# power_supply.net
KiCad netlist of a schematic drawn in Altium Designer
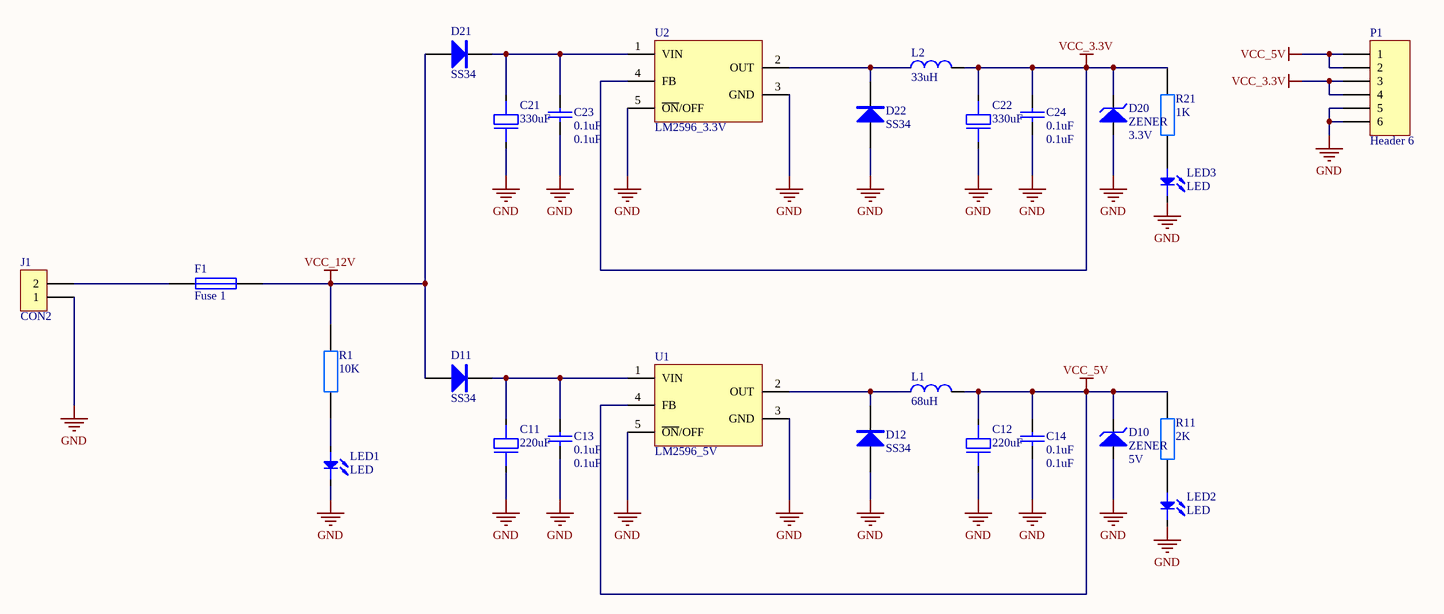
[diagram p0: power supply.SchDoc]

(export (version "E")
  (design (tool "Eeschema 10.0.6"))
  (components
    (comp (ref "C11")
      (value "220uF")
      (footprint "SMD-EC-F10")
      (libsource (lib "common") (part "Electrolytic CAP"))
    )
    (comp (ref "C12")
      (value "220uF")
      (footprint "SMD-EC-F10")
      (libsource (lib "common") (part "Electrolytic CAP"))
    )
    (comp (ref "C13")
      (value "0.1uF")
      (footprint "0805C")
      (fields (field (name "ALTIUM_VALUE") "0.1uF"))
      (libsource (lib "common") (part "CAP"))
    )
    (comp (ref "C14")
      (value "0.1uF")
      (footprint "0805C")
      (fields (field (name "ALTIUM_VALUE") "0.1uF"))
      (libsource (lib "common") (part "CAP"))
    )
    (comp (ref "C21")
      (value "330uF")
      (footprint "SMD-EC-F10")
      (libsource (lib "common") (part "Electrolytic CAP"))
    )
    (comp (ref "C22")
      (value "330uF")
      (footprint "SMD-EC-F10")
      (libsource (lib "common") (part "Electrolytic CAP"))
    )
    (comp (ref "C23")
      (value "0.1uF")
      (footprint "0805C")
      (fields (field (name "ALTIUM_VALUE") "0.1uF"))
      (libsource (lib "common") (part "CAP"))
    )
    (comp (ref "C24")
      (value "0.1uF")
      (footprint "0805C")
      (fields (field (name "ALTIUM_VALUE") "0.1uF"))
      (libsource (lib "common") (part "CAP"))
    )
    (comp (ref "D10")
      (value "ZENER")
      (footprint "1206D")
      (fields (field (name "ALTIUM_VALUE") "5V"))
      (libsource (lib "common") (part "ZENER"))
    )
    (comp (ref "D11")
      (value "SS34")
      (footprint "SMA")
      (description "Diode")
      (libsource (lib "common") (part "SS14"))
    )
    (comp (ref "D12")
      (value "SS34")
      (footprint "SMA")
      (description "Diode")
      (libsource (lib "common") (part "SS14"))
    )
    (comp (ref "D20")
      (value "ZENER")
      (footprint "1206D")
      (fields (field (name "ALTIUM_VALUE") "3.3V"))
      (libsource (lib "common") (part "ZENER"))
    )
    (comp (ref "D21")
      (value "SS34")
      (footprint "SMA")
      (description "Diode")
      (libsource (lib "common") (part "SS14"))
    )
    (comp (ref "D22")
      (value "SS34")
      (footprint "SMA")
      (description "Diode")
      (libsource (lib "common") (part "SS14"))
    )
    (comp (ref "F1")
      (value "Fuse 1")
      (footprint "FUSE1")
      (description "Fuse")
      (fields (field (name "PUBLISHER") "Altium Limited"))
      (libsource (lib "common") (part "Fuse 1"))
    )
    (comp (ref "J1") (value "CON2") (footprint "con2") (libsource (lib "common") (part "CON2")))
    (comp (ref "L1") (value "68uH") (footprint "12x12") (libsource (lib "common") (part "Inductance")))
    (comp (ref "L2") (value "33uH") (footprint "12x12") (libsource (lib "common") (part "Inductance")))
    (comp (ref "LED1") (value "LED") (footprint "3528 led") (libsource (lib "common") (part "LED")))
    (comp (ref "LED2") (value "LED") (footprint "3528 led") (libsource (lib "common") (part "LED")))
    (comp (ref "LED3") (value "LED") (footprint "3528 led") (libsource (lib "common") (part "LED")))
    (comp (ref "P1")
      (value "Header 6")
      (footprint "HDR1X6")
      (description "Header, 6-Pin")
      (fields (field (name "PUBLISHER") "Altium Limited"))
      (libsource (lib "Miscellaneous Connectors") (part "Header 6"))
    )
    (comp (ref "R1")
      (value "10K")
      (footprint "0805")
      (description "RES")
      (libsource (lib "common") (part "RES"))
    )
    (comp (ref "R11")
      (value "2K")
      (footprint "0805")
      (description "RES")
      (libsource (lib "common") (part "RES"))
    )
    (comp (ref "R21")
      (value "1K")
      (footprint "0805")
      (description "RES")
      (libsource (lib "common") (part "RES"))
    )
    (comp (ref "U1")
      (value "LM2596_5V")
      (footprint "平面IC:TO-263")
      (description "IC-power")
      (libsource (lib "common") (part "LM2596"))
    )
    (comp (ref "U2")
      (value "LM2596_3.3V")
      (footprint "平面IC:to-263")
      (description "IC-power")
      (libsource (lib "common") (part "LM2596"))
    )
  )
  (nets
    (net (code "1") (name "GND") (class "Default")
      (node (ref "C11") (pin "2") (pinfunction "2_2") (pintype "passive"))
      (node (ref "C12") (pin "2") (pinfunction "2_2") (pintype "passive"))
      (node (ref "C13") (pin "2") (pinfunction "2_2") (pintype "passive"))
      (node (ref "C14") (pin "2") (pinfunction "2_2") (pintype "passive"))
      (node (ref "C21") (pin "2") (pinfunction "2_2") (pintype "passive"))
      (node (ref "C22") (pin "2") (pinfunction "2_2") (pintype "passive"))
      (node (ref "C23") (pin "2") (pinfunction "2_2") (pintype "passive"))
      (node (ref "C24") (pin "2") (pinfunction "2_2") (pintype "passive"))
      (node (ref "D10") (pin "1") (pinfunction "A_1") (pintype "passive"))
      (node (ref "D12") (pin "1") (pinfunction "A_1") (pintype "passive"))
      (node (ref "D20") (pin "1") (pinfunction "A_1") (pintype "passive"))
      (node (ref "D22") (pin "1") (pinfunction "A_1") (pintype "passive"))
      (node (ref "J1") (pin "1") (pinfunction "1_1") (pintype "passive"))
      (node (ref "LED1") (pin "2") (pintype "passive"))
      (node (ref "LED2") (pin "2") (pintype "passive"))
      (node (ref "LED3") (pin "2") (pintype "passive"))
      (node (ref "P1") (pin "5") (pinfunction "5_5") (pintype "passive"))
      (node (ref "P1") (pin "6") (pinfunction "6_6") (pintype "passive"))
      (node (ref "U1") (pin "3") (pinfunction "GND_3") (pintype "passive"))
      (node (ref "U1") (pin "5") (pinfunction "~{ON}/OFF_5") (pintype "passive"))
      (node (ref "U2") (pin "3") (pinfunction "GND_3") (pintype "passive"))
      (node (ref "U2") (pin "5") (pinfunction "~{ON}/OFF_5") (pintype "passive"))
    )
    (net (code "2") (name "Net-(D11-K)") (class "Default")
      (node (ref "C11") (pin "1") (pinfunction "1_1") (pintype "passive"))
      (node (ref "C13") (pin "1") (pinfunction "1_1") (pintype "passive"))
      (node (ref "D11") (pin "2") (pinfunction "K_2") (pintype "passive"))
      (node (ref "U1") (pin "1") (pinfunction "VIN_1") (pintype "passive"))
    )
    (net (code "3") (name "Net-(D12-K)") (class "Default")
      (node (ref "D12") (pin "2") (pinfunction "K_2") (pintype "passive"))
      (node (ref "L1") (pin "2") (pinfunction "2_2") (pintype "passive"))
      (node (ref "U1") (pin "2") (pinfunction "OUT_2") (pintype "passive"))
    )
    (net (code "4") (name "Net-(D21-K)") (class "Default")
      (node (ref "C21") (pin "1") (pinfunction "1_1") (pintype "passive"))
      (node (ref "C23") (pin "1") (pinfunction "1_1") (pintype "passive"))
      (node (ref "D21") (pin "2") (pinfunction "K_2") (pintype "passive"))
      (node (ref "U2") (pin "1") (pinfunction "VIN_1") (pintype "passive"))
    )
    (net (code "5") (name "Net-(D22-K)") (class "Default")
      (node (ref "D22") (pin "2") (pinfunction "K_2") (pintype "passive"))
      (node (ref "L2") (pin "2") (pinfunction "2_2") (pintype "passive"))
      (node (ref "U2") (pin "2") (pinfunction "OUT_2") (pintype "passive"))
    )
    (net (code "6") (name "Net-(F1-Pad1)") (class "Default")
      (node (ref "F1") (pin "1") (pinfunction "1_1") (pintype "passive"))
      (node (ref "J1") (pin "2") (pinfunction "2_2") (pintype "passive"))
    )
    (net (code "7") (name "Net-(LED1-Pad1)") (class "Default")
      (node (ref "LED1") (pin "1") (pintype "passive"))
      (node (ref "R1") (pin "1") (pinfunction "1_1") (pintype "passive"))
    )
    (net (code "8") (name "Net-(LED2-Pad1)") (class "Default")
      (node (ref "LED2") (pin "1") (pintype "passive"))
      (node (ref "R11") (pin "1") (pinfunction "1_1") (pintype "passive"))
    )
    (net (code "9") (name "Net-(LED3-Pad1)") (class "Default")
      (node (ref "LED3") (pin "1") (pintype "passive"))
      (node (ref "R21") (pin "1") (pinfunction "1_1") (pintype "passive"))
    )
    (net (code "10") (name "VCC_3.3V") (class "Default")
      (node (ref "C22") (pin "1") (pinfunction "1_1") (pintype "passive"))
      (node (ref "C24") (pin "1") (pinfunction "1_1") (pintype "passive"))
      (node (ref "D20") (pin "2") (pinfunction "K_2") (pintype "passive"))
      (node (ref "L2") (pin "1") (pinfunction "1_1") (pintype "passive"))
      (node (ref "P1") (pin "3") (pinfunction "3_3") (pintype "passive"))
      (node (ref "P1") (pin "4") (pinfunction "4_4") (pintype "passive"))
      (node (ref "R21") (pin "2") (pinfunction "2_2") (pintype "passive"))
      (node (ref "U2") (pin "4") (pinfunction "FB_4") (pintype "passive"))
    )
    (net (code "11") (name "VCC_5V") (class "Default")
      (node (ref "C12") (pin "1") (pinfunction "1_1") (pintype "passive"))
      (node (ref "C14") (pin "1") (pinfunction "1_1") (pintype "passive"))
      (node (ref "D10") (pin "2") (pinfunction "K_2") (pintype "passive"))
      (node (ref "L1") (pin "1") (pinfunction "1_1") (pintype "passive"))
      (node (ref "P1") (pin "1") (pinfunction "1_1") (pintype "passive"))
      (node (ref "P1") (pin "2") (pinfunction "2_2") (pintype "passive"))
      (node (ref "R11") (pin "2") (pinfunction "2_2") (pintype "passive"))
      (node (ref "U1") (pin "4") (pinfunction "FB_4") (pintype "passive"))
    )
    (net (code "12") (name "VCC_12V") (class "Default")
      (node (ref "D11") (pin "1") (pinfunction "A_1") (pintype "passive"))
      (node (ref "D21") (pin "1") (pinfunction "A_1") (pintype "passive"))
      (node (ref "F1") (pin "2") (pinfunction "2_2") (pintype "passive"))
      (node (ref "R1") (pin "2") (pinfunction "2_2") (pintype "passive"))
    )
  )
)
